# atmega328p.net
KiCad netlist of a schematic drawn in EAGLE
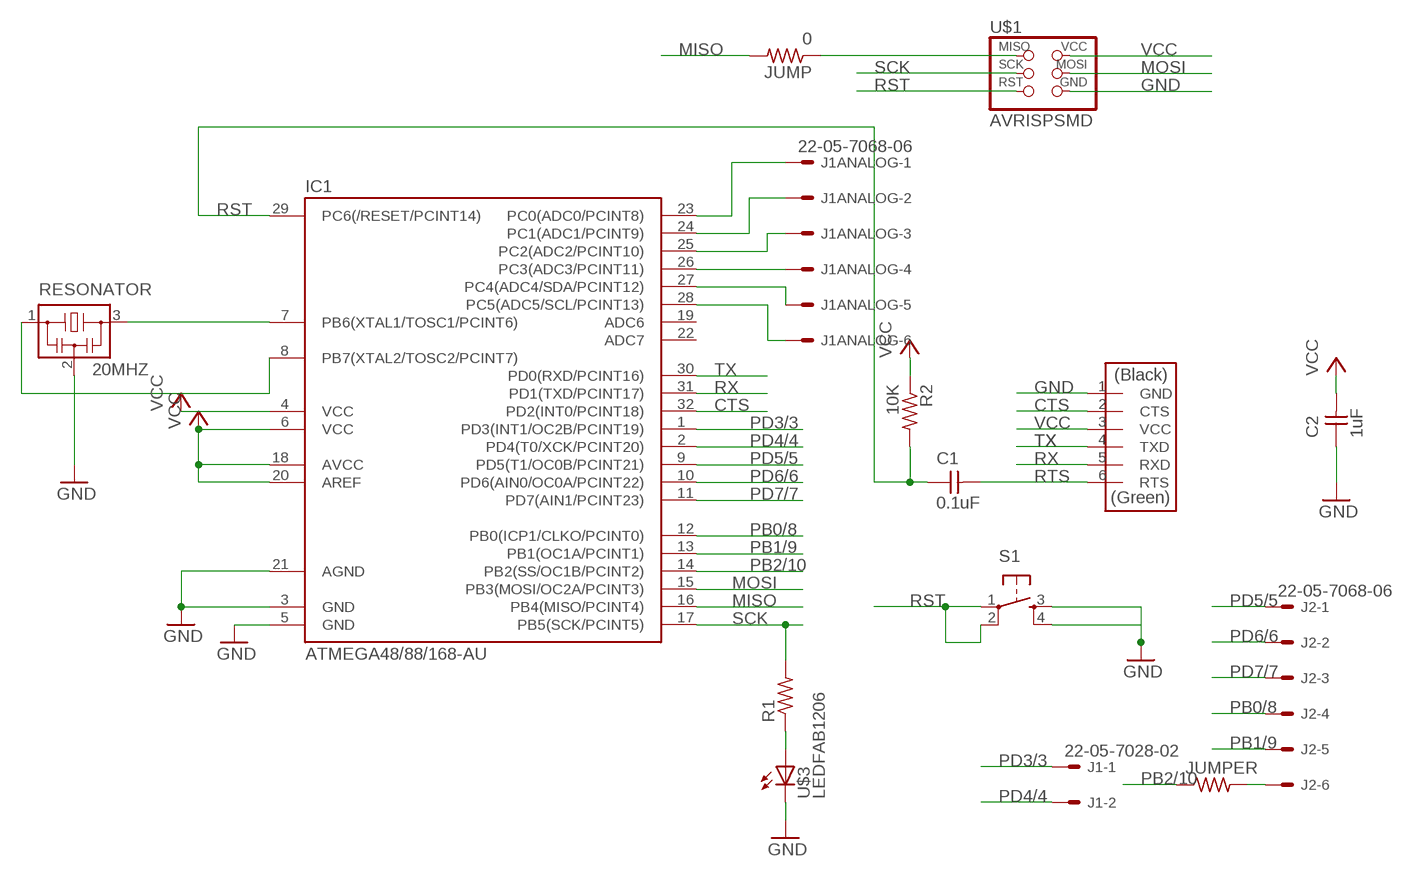
[diagram p0: schematic, sheet 1]

(export (version "E")
  (design (tool "Eeschema 10.0.6"))
  (components
    (comp (ref "C1")
      (value "0.1uF")
      (footprint "eagle-import:C1206FAB")
      (libsource (lib "eagle-import") (part "CAP-UNPOLARIZEDFAB"))
    )
    (comp (ref "C2")
      (value "1uF")
      (footprint "eagle-import:C1206FAB")
      (libsource (lib "eagle-import") (part "CAP-UNPOLARIZEDFAB"))
    )
    (comp (ref "IC1")
      (value "ATMEGA48/88/168-AU")
      (footprint "eagle-import:TQFP32-08")
      (libsource (lib "eagle-import") (part "ATMEGA48/88/168-AU"))
    )
    (comp (ref "J1")
      (value "22-05-7028-02")
      (footprint "eagle-import:7395-02")
      (libsource (lib "eagle-import") (part "22-?-0205-7028"))
    )
    (comp (ref "J1ANALOG")
      (value "22-05-7068-06")
      (footprint "eagle-import:7395-06")
      (libsource (lib "eagle-import") (part "22-?-0605-7068"))
    )
    (comp (ref "J2")
      (value "22-05-7068-06")
      (footprint "eagle-import:7395-06")
      (libsource (lib "eagle-import") (part "22-?-0605-7068"))
    )
    (comp (ref "JUMP")
      (value "0")
      (footprint "eagle-import:R1206FAB")
      (libsource (lib "eagle-import") (part "RES-US1206FAB"))
    )
    (comp (ref "JUMPER")
      (value "RES-US1206FAB")
      (footprint "eagle-import:R1206FAB")
      (libsource (lib "eagle-import") (part "RES-US1206FAB"))
    )
    (comp (ref "R1")
      (value "RES-US1206FAB")
      (footprint "eagle-import:R1206FAB")
      (libsource (lib "eagle-import") (part "RES-US1206FAB"))
    )
    (comp (ref "R2")
      (value "10K")
      (footprint "eagle-import:R1206FAB")
      (libsource (lib "eagle-import") (part "RES-US1206FAB"))
    )
    (comp (ref "RESONATOR")
      (value "20MHZ")
      (footprint "eagle-import:EFOBM")
      (libsource (lib "eagle-import") (part "RESONATOR"))
    )
    (comp (ref "S1")
      (value "6MM_SWITCH6MM_SWITCH")
      (footprint "eagle-import:6MM_SWITCH")
      (libsource (lib "eagle-import") (part "6MM_SWITCH6MM_SWITCH"))
    )
    (comp (ref "U$1")
      (value "AVRISPSMD")
      (footprint "eagle-import:2X03SMD")
      (libsource (lib "eagle-import") (part "AVRISPSMD"))
    )
    (comp (ref "U$2")
      (value "FTDI-SMD-HEADER")
      (footprint "eagle-import:1X06SMD")
      (libsource (lib "eagle-import") (part "FTDI-SMD-HEADER"))
    )
    (comp (ref "U$3")
      (value "LEDFAB1206")
      (footprint "eagle-import:LED1206FAB")
      (libsource (lib "eagle-import") (part "LEDFAB1206"))
    )
  )
  (nets
    (net (code "1") (name "/CTS") (class "Default")
      (node (ref "IC1") (pin "32") (pinfunction "PD2(INT0/PCINT18)_32") (pintype "bidirectional"))
      (node (ref "U$2") (pin "2") (pinfunction "CTS_2") (pintype "bidirectional"))
    )
    (net (code "2") (name "/MISO") (class "Default")
      (node (ref "IC1") (pin "16") (pinfunction "PB4(MISO/PCINT4)_16") (pintype "bidirectional"))
      (node (ref "JUMP") (pin "2") (pinfunction "2_2") (pintype "passive"))
    )
    (net (code "3") (name "/MOSI") (class "Default")
      (node (ref "IC1") (pin "15") (pinfunction "PB3(MOSI/OC2A/PCINT3)_15") (pintype "bidirectional"))
      (node (ref "U$1") (pin "4") (pinfunction "MOSI_4") (pintype "passive"))
    )
    (net (code "4") (name "/PB0{slash}8") (class "Default")
      (node (ref "IC1") (pin "12") (pinfunction "PB0(ICP1/CLKO/PCINT0)_12") (pintype "bidirectional"))
      (node (ref "J2") (pin "4") (pinfunction "S_4") (pintype "passive"))
    )
    (net (code "5") (name "/PB1{slash}9") (class "Default")
      (node (ref "IC1") (pin "13") (pinfunction "PB1(OC1A/PCINT1)_13") (pintype "bidirectional"))
      (node (ref "J2") (pin "5") (pinfunction "S_5") (pintype "passive"))
    )
    (net (code "6") (name "/PB2{slash}10") (class "Default")
      (node (ref "IC1") (pin "14") (pinfunction "PB2(SS/OC1B/PCINT2)_14") (pintype "bidirectional"))
      (node (ref "JUMPER") (pin "1") (pinfunction "1_1") (pintype "passive"))
    )
    (net (code "7") (name "/PD3{slash}3") (class "Default")
      (node (ref "IC1") (pin "1") (pinfunction "PD3(INT1/OC2B/PCINT19)_1") (pintype "bidirectional"))
      (node (ref "J1") (pin "1") (pinfunction "S_1") (pintype "passive"))
    )
    (net (code "8") (name "/PD4{slash}4") (class "Default")
      (node (ref "IC1") (pin "2") (pinfunction "PD4(T0/XCK/PCINT20)_2") (pintype "bidirectional"))
      (node (ref "J1") (pin "2") (pinfunction "S_2") (pintype "passive"))
    )
    (net (code "9") (name "/PD5{slash}5") (class "Default")
      (node (ref "IC1") (pin "9") (pinfunction "PD5(T1/OC0B/PCINT21)_9") (pintype "bidirectional"))
      (node (ref "J2") (pin "1") (pinfunction "S_1") (pintype "passive"))
    )
    (net (code "10") (name "/PD6{slash}6") (class "Default")
      (node (ref "IC1") (pin "10") (pinfunction "PD6(AIN0/OC0A/PCINT22)_10") (pintype "bidirectional"))
      (node (ref "J2") (pin "2") (pinfunction "S_2") (pintype "passive"))
    )
    (net (code "11") (name "/PD7{slash}7") (class "Default")
      (node (ref "IC1") (pin "11") (pinfunction "PD7(AIN1/PCINT23)_11") (pintype "bidirectional"))
      (node (ref "J2") (pin "3") (pinfunction "S_3") (pintype "passive"))
    )
    (net (code "12") (name "/RST") (class "Default")
      (node (ref "C1") (pin "1") (pinfunction "1_1") (pintype "passive"))
      (node (ref "IC1") (pin "29") (pinfunction "PC6(/RESET/PCINT14)_29") (pintype "bidirectional"))
      (node (ref "R2") (pin "2") (pinfunction "2_2") (pintype "passive"))
      (node (ref "S1") (pin "1") (pinfunction "P_1") (pintype "passive"))
      (node (ref "S1") (pin "2") (pinfunction "P1_2") (pintype "passive"))
      (node (ref "U$1") (pin "5") (pinfunction "RST_5") (pintype "passive"))
    )
    (net (code "13") (name "/RTS") (class "Default")
      (node (ref "C1") (pin "2") (pinfunction "2_2") (pintype "passive"))
      (node (ref "U$2") (pin "6") (pinfunction "RTS_6") (pintype "bidirectional"))
    )
    (net (code "14") (name "/RX") (class "Default")
      (node (ref "IC1") (pin "31") (pinfunction "PD1(TXD/PCINT17)_31") (pintype "bidirectional"))
      (node (ref "U$2") (pin "5") (pinfunction "RXD_5") (pintype "bidirectional"))
    )
    (net (code "15") (name "/SCK") (class "Default")
      (node (ref "IC1") (pin "17") (pinfunction "PB5(SCK/PCINT5)_17") (pintype "bidirectional"))
      (node (ref "R1") (pin "2") (pinfunction "2_2") (pintype "passive"))
      (node (ref "U$1") (pin "3") (pinfunction "SCK_3") (pintype "passive"))
    )
    (net (code "16") (name "/TX") (class "Default")
      (node (ref "IC1") (pin "30") (pinfunction "PD0(RXD/PCINT16)_30") (pintype "bidirectional"))
      (node (ref "U$2") (pin "4") (pinfunction "TXD_4") (pintype "bidirectional"))
    )
    (net (code "17") (name "GND") (class "Default")
      (node (ref "C2") (pin "1") (pinfunction "1_1") (pintype "passive"))
      (node (ref "IC1") (pin "21") (pinfunction "AGND_21") (pintype "power_in"))
      (node (ref "IC1") (pin "3") (pinfunction "GND_3") (pintype "power_in"))
      (node (ref "IC1") (pin "5") (pinfunction "GND_5") (pintype "power_in"))
      (node (ref "RESONATOR") (pin "2") (pinfunction "2_2") (pintype "passive"))
      (node (ref "S1") (pin "3") (pinfunction "S_3") (pintype "passive"))
      (node (ref "S1") (pin "4") (pinfunction "S1_4") (pintype "passive"))
      (node (ref "U$1") (pin "6") (pinfunction "GND_6") (pintype "passive"))
      (node (ref "U$2") (pin "1") (pinfunction "GND_1") (pintype "bidirectional"))
      (node (ref "U$3") (pin "2") (pinfunction "C_2") (pintype "passive"))
    )
    (net (code "18") (name "Net-(IC1-PB6(XTAL1{slash}TOSC1{slash}PCINT6))") (class "Default")
      (node (ref "IC1") (pin "7") (pinfunction "PB6(XTAL1/TOSC1/PCINT6)_7") (pintype "bidirectional"))
      (node (ref "RESONATOR") (pin "3") (pinfunction "3_3") (pintype "passive"))
    )
    (net (code "19") (name "Net-(IC1-PB7(XTAL2{slash}TOSC2{slash}PCINT7))") (class "Default")
      (node (ref "IC1") (pin "8") (pinfunction "PB7(XTAL2/TOSC2/PCINT7)_8") (pintype "bidirectional"))
      (node (ref "RESONATOR") (pin "1") (pinfunction "1_1") (pintype "passive"))
    )
    (net (code "20") (name "Net-(IC1-PC0(ADC0{slash}PCINT8))") (class "Default")
      (node (ref "IC1") (pin "23") (pinfunction "PC0(ADC0/PCINT8)_23") (pintype "bidirectional"))
      (node (ref "J1ANALOG") (pin "1") (pinfunction "S_1") (pintype "passive"))
    )
    (net (code "21") (name "Net-(IC1-PC1(ADC1{slash}PCINT9))") (class "Default")
      (node (ref "IC1") (pin "24") (pinfunction "PC1(ADC1/PCINT9)_24") (pintype "bidirectional"))
      (node (ref "J1ANALOG") (pin "2") (pinfunction "S_2") (pintype "passive"))
    )
    (net (code "22") (name "Net-(IC1-PC2(ADC2{slash}PCINT10))") (class "Default")
      (node (ref "IC1") (pin "25") (pinfunction "PC2(ADC2/PCINT10)_25") (pintype "bidirectional"))
      (node (ref "J1ANALOG") (pin "3") (pinfunction "S_3") (pintype "passive"))
    )
    (net (code "23") (name "Net-(IC1-PC3(ADC3{slash}PCINT11))") (class "Default")
      (node (ref "IC1") (pin "26") (pinfunction "PC3(ADC3/PCINT11)_26") (pintype "bidirectional"))
      (node (ref "J1ANALOG") (pin "4") (pinfunction "S_4") (pintype "passive"))
    )
    (net (code "24") (name "Net-(IC1-PC4(ADC4{slash}SDA{slash}PCINT12))") (class "Default")
      (node (ref "IC1") (pin "27") (pinfunction "PC4(ADC4/SDA/PCINT12)_27") (pintype "bidirectional"))
      (node (ref "J1ANALOG") (pin "5") (pinfunction "S_5") (pintype "passive"))
    )
    (net (code "25") (name "Net-(IC1-PC5(ADC5{slash}SCL{slash}PCINT13))") (class "Default")
      (node (ref "IC1") (pin "28") (pinfunction "PC5(ADC5/SCL/PCINT13)_28") (pintype "bidirectional"))
      (node (ref "J1ANALOG") (pin "6") (pinfunction "S_6") (pintype "passive"))
    )
    (net (code "26") (name "Net-(J2F-S)") (class "Default")
      (node (ref "J2") (pin "6") (pinfunction "S_6") (pintype "passive"))
      (node (ref "JUMPER") (pin "2") (pinfunction "2_2") (pintype "passive"))
    )
    (net (code "27") (name "Net-(U$1-MISO)") (class "Default")
      (node (ref "JUMP") (pin "1") (pinfunction "1_1") (pintype "passive"))
      (node (ref "U$1") (pin "1") (pinfunction "MISO_1") (pintype "passive"))
    )
    (net (code "28") (name "Net-(U$3-A)") (class "Default")
      (node (ref "R1") (pin "1") (pinfunction "1_1") (pintype "passive"))
      (node (ref "U$3") (pin "1") (pinfunction "A_1") (pintype "passive"))
    )
    (net (code "29") (name "VCC") (class "Default")
      (node (ref "C2") (pin "2") (pinfunction "2_2") (pintype "passive"))
      (node (ref "IC1") (pin "18") (pinfunction "AVCC_18") (pintype "passive"))
      (node (ref "IC1") (pin "20") (pinfunction "AREF_20") (pintype "passive"))
      (node (ref "IC1") (pin "4") (pinfunction "VCC_4") (pintype "power_in"))
      (node (ref "IC1") (pin "6") (pinfunction "VCC_6") (pintype "power_in"))
      (node (ref "R2") (pin "1") (pinfunction "1_1") (pintype "passive"))
      (node (ref "U$1") (pin "2") (pinfunction "VCC_2") (pintype "passive"))
      (node (ref "U$2") (pin "3") (pinfunction "VCC_3") (pintype "bidirectional"))
    )
    (net (code "30") (name "unconnected-(IC1-ADC6-Pad19)") (class "Default")
      (node (ref "IC1") (pin "19") (pinfunction "ADC6_19") (pintype "passive"))
    )
    (net (code "31") (name "unconnected-(IC1-ADC7-Pad22)") (class "Default")
      (node (ref "IC1") (pin "22") (pinfunction "ADC7_22") (pintype "passive"))
    )
  )
)
